# Zynq-Power.net
KiCad netlist of a schematic drawn in Altium Designer
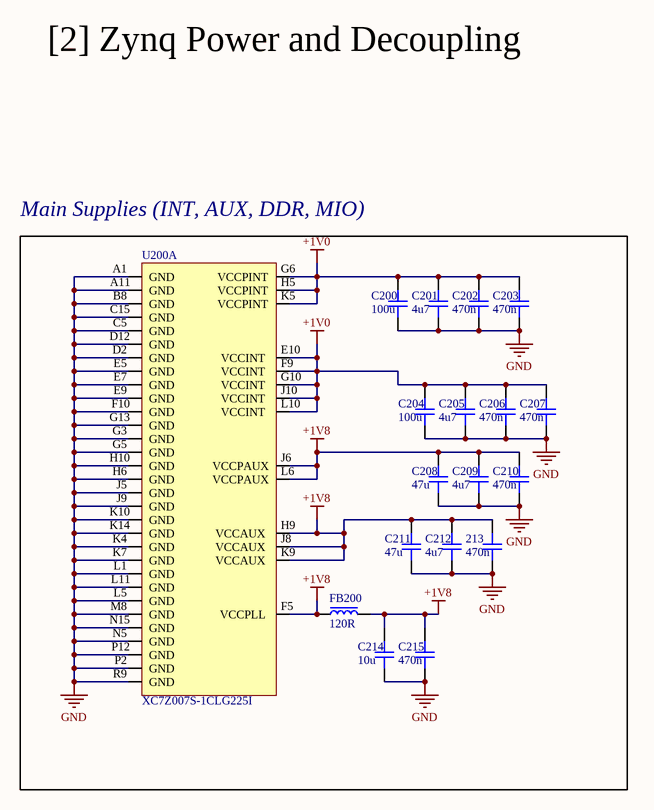
[diagram p0: Zynq-Power.SchDoc]

(export (version "E")
  (design (tool "Eeschema 10.0.6"))
  (components
    (comp (ref "213")
      (value "470n")
      (footprint "CAP_1210")
      (description "Capacitor SMD 1210")
      (libsource (lib "Schematic-Lib-PhilsLab") (part "CAP_1210"))
    )
    (comp (ref "C200")
      (value "100u")
      (footprint "CAP_1210")
      (description "Capacitor SMD 1210")
      (libsource (lib "Schematic-Lib-PhilsLab") (part "CAP_1210"))
    )
    (comp (ref "C201")
      (value "4u7")
      (footprint "CAP_1210")
      (description "Capacitor SMD 1210")
      (libsource (lib "Schematic-Lib-PhilsLab") (part "CAP_1210"))
    )
    (comp (ref "C202")
      (value "470n")
      (footprint "CAP_1210")
      (description "Capacitor SMD 1210")
      (libsource (lib "Schematic-Lib-PhilsLab") (part "CAP_1210"))
    )
    (comp (ref "C203")
      (value "470n")
      (footprint "CAP_1210")
      (description "Capacitor SMD 1210")
      (libsource (lib "Schematic-Lib-PhilsLab") (part "CAP_1210"))
    )
    (comp (ref "C204")
      (value "100u")
      (footprint "CAP_1210")
      (description "Capacitor SMD 1210")
      (libsource (lib "Schematic-Lib-PhilsLab") (part "CAP_1210"))
    )
    (comp (ref "C205")
      (value "4u7")
      (footprint "CAP_1210")
      (description "Capacitor SMD 1210")
      (libsource (lib "Schematic-Lib-PhilsLab") (part "CAP_1210"))
    )
    (comp (ref "C206")
      (value "470n")
      (footprint "CAP_1210")
      (description "Capacitor SMD 1210")
      (libsource (lib "Schematic-Lib-PhilsLab") (part "CAP_1210"))
    )
    (comp (ref "C207")
      (value "470n")
      (footprint "CAP_1210")
      (description "Capacitor SMD 1210")
      (libsource (lib "Schematic-Lib-PhilsLab") (part "CAP_1210"))
    )
    (comp (ref "C208")
      (value "47u")
      (footprint "CAP_1210")
      (description "Capacitor SMD 1210")
      (libsource (lib "Schematic-Lib-PhilsLab") (part "CAP_1210"))
    )
    (comp (ref "C209")
      (value "4u7")
      (footprint "CAP_1210")
      (description "Capacitor SMD 1210")
      (libsource (lib "Schematic-Lib-PhilsLab") (part "CAP_1210"))
    )
    (comp (ref "C210")
      (value "470n")
      (footprint "CAP_1210")
      (description "Capacitor SMD 1210")
      (libsource (lib "Schematic-Lib-PhilsLab") (part "CAP_1210"))
    )
    (comp (ref "C211")
      (value "47u")
      (footprint "CAP_1210")
      (description "Capacitor SMD 1210")
      (libsource (lib "Schematic-Lib-PhilsLab") (part "CAP_1210"))
    )
    (comp (ref "C212")
      (value "4u7")
      (footprint "CAP_1210")
      (description "Capacitor SMD 1210")
      (libsource (lib "Schematic-Lib-PhilsLab") (part "CAP_1210"))
    )
    (comp (ref "C214")
      (value "10u")
      (footprint "CAP_1210")
      (description "Capacitor SMD 1210")
      (libsource (lib "Schematic-Lib-PhilsLab") (part "CAP_1210"))
    )
    (comp (ref "C215")
      (value "470n")
      (footprint "CAP_1210")
      (description "Capacitor SMD 1210")
      (libsource (lib "Schematic-Lib-PhilsLab") (part "CAP_1210"))
    )
    (comp (ref "FB200")
      (value "120R")
      (footprint "FB_0402")
      (description "Ferrite Bead SMD 0402")
      (libsource (lib "Schematic-Lib-PhilsLab") (part "FB_0402"))
    )
    (comp (ref "U200")
      (value "XC7Z007S-1CLG225I")
      (footprint "CLG225")
      (description "Xilinx FPGA SoC Zynq 7-Series XC7Z007S CLG255 Package Industrial Temperature Grade")
      (fields (field (name "MANUFACTURER") "Xilinx"))
      (libsource (lib "Schematic-Lib-PhilsLab") (part "XC7Z007S-1CLG225I"))
    )
  )
  (nets
    (net (code "1") (name "+1V0") (class "Default")
      (node (ref "C200") (pin "2") (pinfunction "2_2") (pintype "passive"))
      (node (ref "C201") (pin "2") (pinfunction "2_2") (pintype "passive"))
      (node (ref "C202") (pin "2") (pinfunction "2_2") (pintype "passive"))
      (node (ref "C203") (pin "2") (pinfunction "2_2") (pintype "passive"))
      (node (ref "C204") (pin "2") (pinfunction "2_2") (pintype "passive"))
      (node (ref "C205") (pin "2") (pinfunction "2_2") (pintype "passive"))
      (node (ref "C206") (pin "2") (pinfunction "2_2") (pintype "passive"))
      (node (ref "C207") (pin "2") (pinfunction "2_2") (pintype "passive"))
      (node (ref "U200") (pin "E10") (pinfunction "VCCINT_E10") (pintype "passive"))
      (node (ref "U200") (pin "F9") (pinfunction "VCCINT_F9") (pintype "passive"))
      (node (ref "U200") (pin "G10") (pinfunction "VCCINT_G10") (pintype "passive"))
      (node (ref "U200") (pin "G6") (pinfunction "VCCPINT_G6") (pintype "passive"))
      (node (ref "U200") (pin "H5") (pinfunction "VCCPINT_H5") (pintype "passive"))
      (node (ref "U200") (pin "J10") (pinfunction "VCCINT_J10") (pintype "passive"))
      (node (ref "U200") (pin "K5") (pinfunction "VCCPINT_K5") (pintype "passive"))
      (node (ref "U200") (pin "L10") (pinfunction "VCCINT_L10") (pintype "passive"))
    )
    (net (code "2") (name "+1V8") (class "Default")
      (node (ref "213") (pin "2") (pinfunction "2_2") (pintype "passive"))
      (node (ref "C208") (pin "2") (pinfunction "2_2") (pintype "passive"))
      (node (ref "C209") (pin "2") (pinfunction "2_2") (pintype "passive"))
      (node (ref "C210") (pin "2") (pinfunction "2_2") (pintype "passive"))
      (node (ref "C211") (pin "2") (pinfunction "2_2") (pintype "passive"))
      (node (ref "C212") (pin "2") (pinfunction "2_2") (pintype "passive"))
      (node (ref "C214") (pin "2") (pinfunction "2_2") (pintype "passive"))
      (node (ref "C215") (pin "2") (pinfunction "2_2") (pintype "passive"))
      (node (ref "FB200") (pin "1") (pinfunction "1_1") (pintype "passive"))
      (node (ref "FB200") (pin "2") (pinfunction "2_2") (pintype "passive"))
      (node (ref "U200") (pin "F5") (pinfunction "VCCPLL_F5") (pintype "passive"))
      (node (ref "U200") (pin "H9") (pinfunction "VCCAUX_H9") (pintype "passive"))
      (node (ref "U200") (pin "J6") (pinfunction "VCCPAUX_J6") (pintype "passive"))
      (node (ref "U200") (pin "J8") (pinfunction "VCCAUX_J8") (pintype "passive"))
      (node (ref "U200") (pin "K9") (pinfunction "VCCAUX_K9") (pintype "passive"))
      (node (ref "U200") (pin "L6") (pinfunction "VCCPAUX_L6") (pintype "passive"))
    )
    (net (code "3") (name "GND") (class "Default")
      (node (ref "213") (pin "1") (pinfunction "1_1") (pintype "passive"))
      (node (ref "C200") (pin "1") (pinfunction "1_1") (pintype "passive"))
      (node (ref "C201") (pin "1") (pinfunction "1_1") (pintype "passive"))
      (node (ref "C202") (pin "1") (pinfunction "1_1") (pintype "passive"))
      (node (ref "C203") (pin "1") (pinfunction "1_1") (pintype "passive"))
      (node (ref "C204") (pin "1") (pinfunction "1_1") (pintype "passive"))
      (node (ref "C205") (pin "1") (pinfunction "1_1") (pintype "passive"))
      (node (ref "C206") (pin "1") (pinfunction "1_1") (pintype "passive"))
      (node (ref "C207") (pin "1") (pinfunction "1_1") (pintype "passive"))
      (node (ref "C208") (pin "1") (pinfunction "1_1") (pintype "passive"))
      (node (ref "C209") (pin "1") (pinfunction "1_1") (pintype "passive"))
      (node (ref "C210") (pin "1") (pinfunction "1_1") (pintype "passive"))
      (node (ref "C211") (pin "1") (pinfunction "1_1") (pintype "passive"))
      (node (ref "C212") (pin "1") (pinfunction "1_1") (pintype "passive"))
      (node (ref "C214") (pin "1") (pinfunction "1_1") (pintype "passive"))
      (node (ref "C215") (pin "1") (pinfunction "1_1") (pintype "passive"))
      (node (ref "U200") (pin "A1") (pinfunction "GND_A1") (pintype "passive"))
      (node (ref "U200") (pin "A11") (pinfunction "GND_A11") (pintype "passive"))
      (node (ref "U200") (pin "B8") (pinfunction "GND_B8") (pintype "passive"))
      (node (ref "U200") (pin "C15") (pinfunction "GND_C15") (pintype "passive"))
      (node (ref "U200") (pin "C5") (pinfunction "GND_C5") (pintype "passive"))
      (node (ref "U200") (pin "D12") (pinfunction "GND_D12") (pintype "passive"))
      (node (ref "U200") (pin "D2") (pinfunction "GND_D2") (pintype "passive"))
      (node (ref "U200") (pin "E5") (pinfunction "GND_E5") (pintype "passive"))
      (node (ref "U200") (pin "E7") (pinfunction "GND_E7") (pintype "passive"))
      (node (ref "U200") (pin "E9") (pinfunction "GND_E9") (pintype "passive"))
      (node (ref "U200") (pin "F10") (pinfunction "GND_F10") (pintype "passive"))
      (node (ref "U200") (pin "G13") (pinfunction "GND_G13") (pintype "passive"))
      (node (ref "U200") (pin "G3") (pinfunction "GND_G3") (pintype "passive"))
      (node (ref "U200") (pin "G5") (pinfunction "GND_G5") (pintype "passive"))
      (node (ref "U200") (pin "H10") (pinfunction "GND_H10") (pintype "passive"))
      (node (ref "U200") (pin "H6") (pinfunction "GND_H6") (pintype "passive"))
      (node (ref "U200") (pin "J5") (pinfunction "GND_J5") (pintype "passive"))
      (node (ref "U200") (pin "J9") (pinfunction "GND_J9") (pintype "passive"))
      (node (ref "U200") (pin "K10") (pinfunction "GND_K10") (pintype "passive"))
      (node (ref "U200") (pin "K14") (pinfunction "GND_K14") (pintype "passive"))
      (node (ref "U200") (pin "K4") (pinfunction "GND_K4") (pintype "passive"))
      (node (ref "U200") (pin "K7") (pinfunction "GND_K7") (pintype "passive"))
      (node (ref "U200") (pin "L1") (pinfunction "GND_L1") (pintype "passive"))
      (node (ref "U200") (pin "L11") (pinfunction "GND_L11") (pintype "passive"))
      (node (ref "U200") (pin "L5") (pinfunction "GND_L5") (pintype "passive"))
      (node (ref "U200") (pin "M8") (pinfunction "GND_M8") (pintype "passive"))
      (node (ref "U200") (pin "N15") (pinfunction "GND_N15") (pintype "passive"))
      (node (ref "U200") (pin "N5") (pinfunction "GND_N5") (pintype "passive"))
      (node (ref "U200") (pin "P12") (pinfunction "GND_P12") (pintype "passive"))
      (node (ref "U200") (pin "P2") (pinfunction "GND_P2") (pintype "passive"))
      (node (ref "U200") (pin "R9") (pinfunction "GND_R9") (pintype "passive"))
    )
  )
)
